# BATTERY.net
KiCad netlist of a schematic drawn in Altium Designer
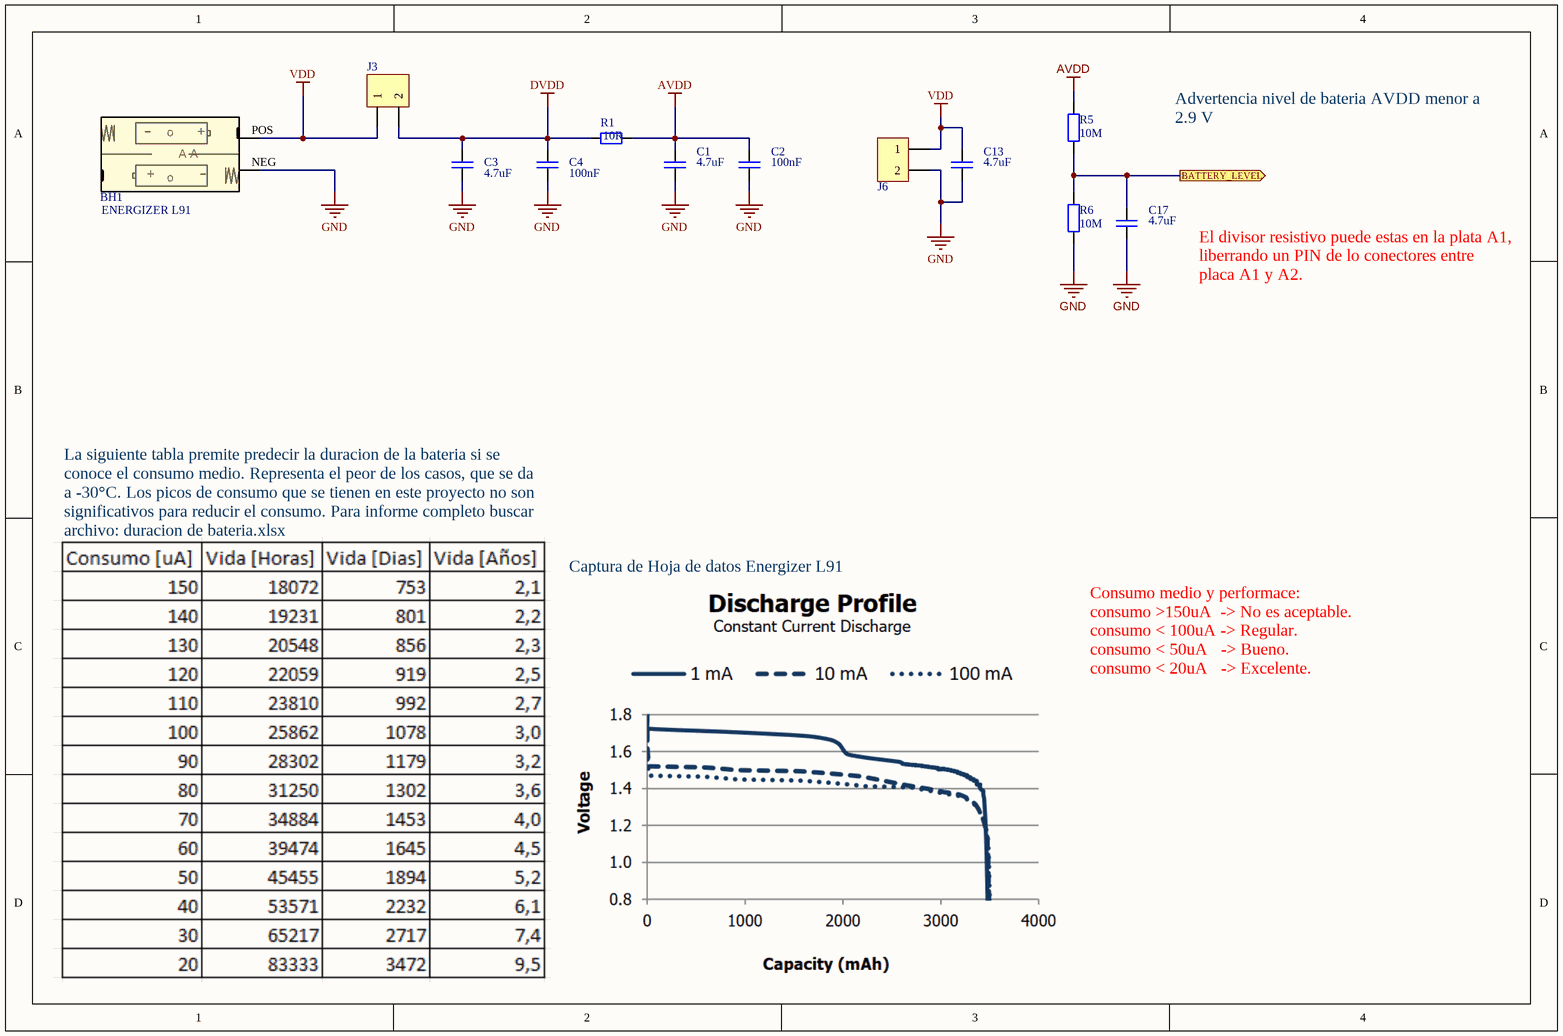
[diagram p0: BATTERY.SchDoc]

(export (version "E")
  (design (tool "Eeschema 10.0.6"))
  (components
    (comp (ref "BH1")
      (value "ENERGIZER L91")
      (footprint "BATTERY_HOLDER_2XAA")
      (description "2 x AA through hole economic type")
      (fields (field (name "MANUFACTURER") "Keystone") (field (name "MANUFACTURER PART NUMBER") "2462"))
      (libsource (lib "Battery_Holders") (part "2462"))
    )
    (comp (ref "C1")
      (value "4.7uF")
      (footprint "CAP_SM0805_YAGEOCC2_N")
      (description "CAP 4.7uF SM0805 X5R 10V YAGEO CC2")
      (fields
        (field (name "MANUFACTURER") "Yageo")
        (field (name "MANUFACTURER PART NUMBER") "CC0805KRX5R6BB475")
      )
      (libsource (lib "Yageo") (part "CC0805KRX5R6BB475"))
    )
    (comp (ref "C2")
      (value "100nF")
      (footprint "CAP_SM0805_YAGEOCC2_N")
      (description "CAP 100nF SM0805 X7R 25V YAGEO CC2")
      (fields
        (field (name "MANUFACTURER") "Yageo")
        (field (name "MANUFACTURER PART NUMBER") "CC0805KRX7R8BB104")
      )
      (libsource (lib "Yageo") (part "CC0805KRX7R8BB104"))
    )
    (comp (ref "C3")
      (value "4.7uF")
      (footprint "CAP_SM0805_YAGEOCC2_N")
      (description "CAP 4.7uF SM0805 X5R 10V YAGEO CC2")
      (fields
        (field (name "MANUFACTURER") "Yageo")
        (field (name "MANUFACTURER PART NUMBER") "CC0805KRX5R6BB475")
      )
      (libsource (lib "Yageo") (part "CC0805KRX5R6BB475"))
    )
    (comp (ref "C4")
      (value "100nF")
      (footprint "CAP_SM0805_YAGEOCC2_N")
      (description "CAP 100nF SM0805 X7R 25V YAGEO CC2")
      (fields
        (field (name "MANUFACTURER") "Yageo")
        (field (name "MANUFACTURER PART NUMBER") "CC0805KRX7R8BB104")
      )
      (libsource (lib "Yageo") (part "CC0805KRX7R8BB104"))
    )
    (comp (ref "C13")
      (value "4.7uF")
      (footprint "CAP_SM0805_YAGEOCC2_N")
      (description "CAP 4.7uF SM0805 X5R 10V YAGEO CC2")
      (fields
        (field (name "MANUFACTURER") "Yageo")
        (field (name "MANUFACTURER PART NUMBER") "CC0805KRX5R6BB475")
      )
      (libsource (lib "Yageo") (part "CC0805KRX5R6BB475"))
    )
    (comp (ref "C17")
      (value "4.7uF")
      (footprint "CAP_SM0805_YAGEOCC2_N")
      (description "CAP 4.7uF SM0805 X5R 10V YAGEO CC2")
      (fields
        (field (name "MANUFACTURER") "Yageo")
        (field (name "MANUFACTURER PART NUMBER") "CC0805KRX5R6BB475")
      )
      (libsource (lib "Yageo") (part "CC0805KRX5R6BB475"))
    )
    (comp (ref "J3")
      (value "Usar Equivalente")
      (footprint "HEADER PIN 1X2")
      (description "1 x 2 - true hole  2.54mm - Pb free")
      (fields
        (field (name "MANUFACTURER") "Amphenol ICC")
        (field (name "MANUFACTURER PART NUMBER") "54101-T0602LF")
      )
      (libsource (lib "header_pin") (part "54101-T0602LF"))
    )
    (comp (ref "J6")
      (value "Usar Equivalente")
      (footprint "HEADER PIN 1X2")
      (description "1 x 2 - true hole  2.54mm - Pb free")
      (fields
        (field (name "MANUFACTURER") "Amphenol ICC")
        (field (name "MANUFACTURER PART NUMBER") "54101-T0602LF")
      )
      (libsource (lib "") (part "54101-T0602LF_1"))
    )
    (comp (ref "R1")
      (value "10R")
      (footprint "RES_SM0805_YAGEORC_N")
      (description "RES 10R SM0805 YAGEO RC_L")
      (fields
        (field (name "MANUFACTURER") "Yageo")
        (field (name "MANUFACTURER PART NUMBER") "RC0805FR-0710RL")
      )
      (libsource (lib "Yageo") (part "RC0805FR-0710RL"))
    )
    (comp (ref "R5")
      (value "10M")
      (footprint "RES_SM0805_YAGEORC_N")
      (description "RES 10M SM0805 YAGEO RC_L")
      (fields
        (field (name "MANUFACTURER") "Yageo")
        (field (name "MANUFACTURER PART NUMBER") "RC0805FR-0710ML")
      )
      (libsource (lib "Yageo") (part "RC0805FR-0710ML"))
    )
    (comp (ref "R6")
      (value "10M")
      (footprint "RES_SM0805_YAGEORC_N")
      (description "RES 10M SM0805 YAGEO RC_L")
      (fields
        (field (name "MANUFACTURER") "Yageo")
        (field (name "MANUFACTURER PART NUMBER") "RC0805FR-0710ML")
      )
      (libsource (lib "Yageo") (part "RC0805FR-0710ML"))
    )
  )
  (nets
    (net (code "1") (name "/BATTERY_LEVEL") (class "Default")
      (node (ref "C17") (pin "1") (pintype "passive"))
      (node (ref "R5") (pin "1") (pintype "passive"))
      (node (ref "R6") (pin "2") (pintype "passive"))
    )
    (net (code "2") (name "AVDD") (class "Default")
      (node (ref "C1") (pin "1") (pintype "passive"))
      (node (ref "C2") (pin "1") (pintype "passive"))
      (node (ref "R1") (pin "2") (pintype "passive"))
      (node (ref "R5") (pin "2") (pintype "passive"))
    )
    (net (code "3") (name "DVDD") (class "Default")
      (node (ref "C3") (pin "1") (pintype "passive"))
      (node (ref "C4") (pin "1") (pintype "passive"))
      (node (ref "J3") (pin "2") (pinfunction "2_2") (pintype "passive"))
      (node (ref "R1") (pin "1") (pintype "passive"))
    )
    (net (code "4") (name "GND") (class "Default")
      (node (ref "BH1") (pin "NEG") (pinfunction "NEG_NEG") (pintype "passive"))
      (node (ref "C1") (pin "2") (pintype "passive"))
      (node (ref "C13") (pin "2") (pintype "passive"))
      (node (ref "C17") (pin "2") (pintype "passive"))
      (node (ref "C2") (pin "2") (pintype "passive"))
      (node (ref "C3") (pin "2") (pintype "passive"))
      (node (ref "C4") (pin "2") (pintype "passive"))
      (node (ref "J6") (pin "2") (pinfunction "2_2") (pintype "passive"))
      (node (ref "R6") (pin "1") (pintype "passive"))
    )
    (net (code "5") (name "VDD") (class "Default")
      (node (ref "BH1") (pin "POS") (pinfunction "POS_POS") (pintype "passive"))
      (node (ref "C13") (pin "1") (pintype "passive"))
      (node (ref "J3") (pin "1") (pinfunction "1_1") (pintype "passive"))
      (node (ref "J6") (pin "1") (pinfunction "1_1") (pintype "passive"))
    )
  )
)
